# ProximitySwitchRelay.net
KiCad netlist of a schematic drawn in EAGLE
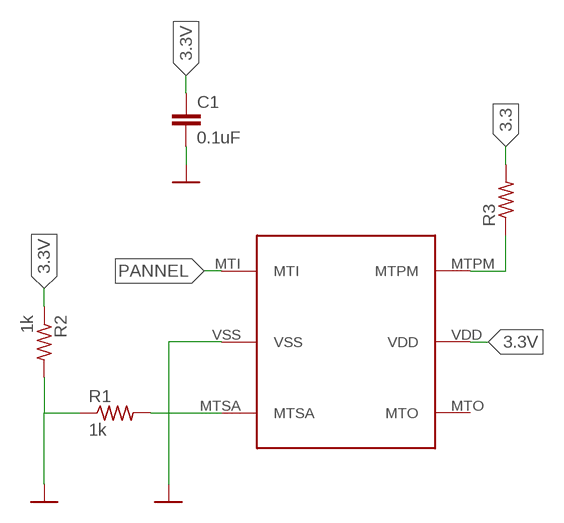
[diagram p0: schematic, sheet 1]

(export (version "E")
  (design (tool "Eeschema 10.0.6"))
  (components
    (comp (ref "C1")
      (value "0.1uF")
      (footprint "eagle-import:CAP-PTH-SMALL-KIT")
      (libsource (lib "eagle-import") (part "0.1UF-KIT-EZ-50V-20%"))
    )
    (comp (ref "R1")
      (value "1k")
      (footprint "eagle-import:RESISTOR_0204_5")
      (libsource (lib "eagle-import") (part "RESISTOR_R-US_0204/5"))
    )
    (comp (ref "R2")
      (value "1k")
      (footprint "eagle-import:RESISTOR_0204_5")
      (libsource (lib "eagle-import") (part "RESISTOR_R-US_0204/5"))
    )
    (comp (ref "R3")
      (value "RESISTOR_R-US_0204/5")
      (footprint "eagle-import:RESISTOR_0204_5")
      (libsource (lib "eagle-import") (part "RESISTOR_R-US_0204/5"))
    )
    (comp (ref "U$1")
      (value "MTCH101")
      (footprint "eagle-import:MTCH101")
      (libsource (lib "eagle-import") (part "MTCH101"))
    )
  )
  (nets
    (net (code "1") (name "3.3") (class "Default")
      (node (ref "R3") (pin "2") (pinfunction "2_2") (pintype "passive"))
    )
    (net (code "2") (name "3.3V") (class "Default")
      (node (ref "C1") (pin "1") (pinfunction "1_1") (pintype "passive"))
      (node (ref "R2") (pin "1") (pinfunction "1_1") (pintype "passive"))
      (node (ref "U$1") (pin "VDD") (pinfunction "VDD_VDD") (pintype "bidirectional"))
    )
    (net (code "3") (name "GND") (class "Default")
      (node (ref "C1") (pin "2") (pinfunction "2_2") (pintype "passive"))
      (node (ref "R1") (pin "1") (pinfunction "1_1") (pintype "passive"))
      (node (ref "R2") (pin "2") (pinfunction "2_2") (pintype "passive"))
      (node (ref "U$1") (pin "VSS") (pinfunction "VSS_VSS") (pintype "bidirectional"))
    )
    (net (code "4") (name "Net-(R1-Pad2)") (class "Default")
      (node (ref "R1") (pin "2") (pinfunction "2_2") (pintype "passive"))
      (node (ref "U$1") (pin "MTSA") (pinfunction "MTSA_MTSA") (pintype "bidirectional"))
    )
    (net (code "5") (name "Net-(R3-Pad1)") (class "Default")
      (node (ref "R3") (pin "1") (pinfunction "1_1") (pintype "passive"))
      (node (ref "U$1") (pin "MTPM") (pinfunction "MTPM_MTPM") (pintype "bidirectional"))
    )
    (net (code "6") (name "PANNEL") (class "Default")
      (node (ref "U$1") (pin "MTI") (pinfunction "MTI_MTI") (pintype "bidirectional"))
    )
    (net (code "7") (name "unconnected-(U$1-PadMTO)") (class "Default")
      (node (ref "U$1") (pin "MTO") (pinfunction "MTO_MTO") (pintype "bidirectional"))
    )
  )
)
